# JSDM_Wemos_DS3231_Single_Layer.net
KiCad netlist of a schematic drawn in EAGLE
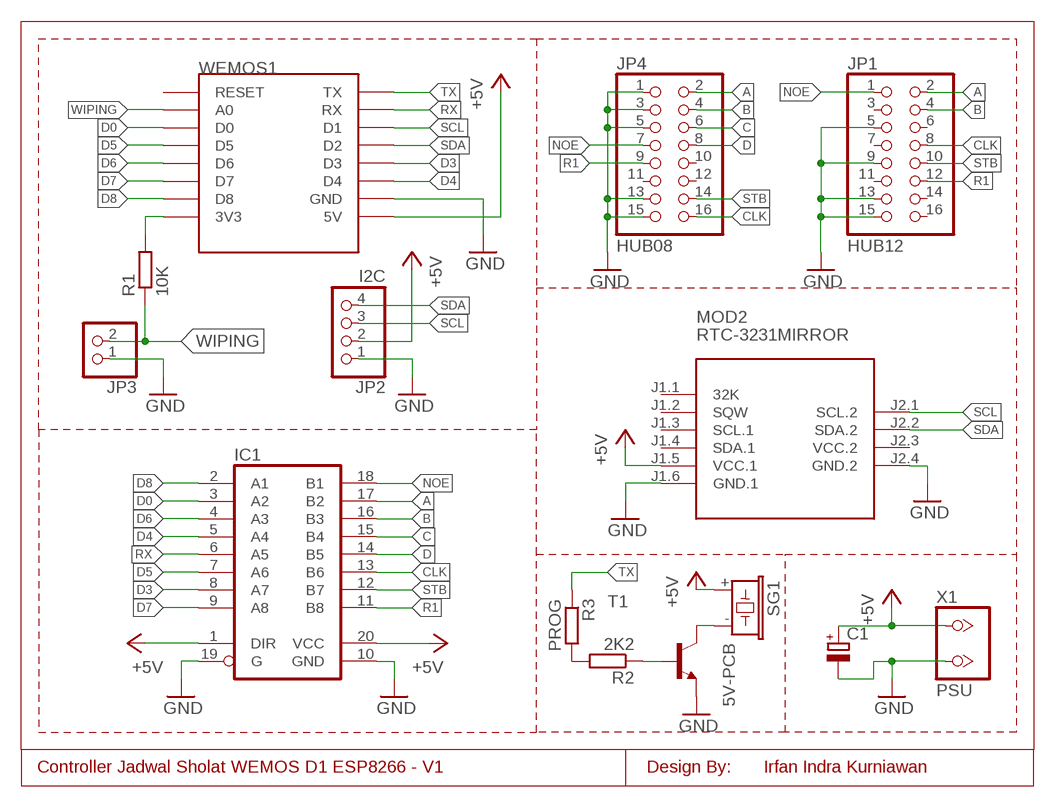
[diagram p0: schematic, sheet 1]

(export (version "E")
  (design (tool "Eeschema 10.0.6"))
  (components
    (comp (ref "C1")
      (value "CPOL-EUE3.5-8")
      (footprint "eagle-import:E3,5-8")
      (libsource (lib "eagle-import") (part "CPOL-EUE3.5-8"))
    )
    (comp (ref "IC1")
      (value "74245SMD")
      (footprint "eagle-import:SO20")
      (libsource (lib "eagle-import") (part "74245SMD"))
    )
    (comp (ref "JP1")
      (value "HUB12")
      (footprint "eagle-import:2X08")
      (libsource (lib "eagle-import") (part "PINHD-2X8"))
    )
    (comp (ref "JP2")
      (value "I2C")
      (footprint "eagle-import:1X04")
      (libsource (lib "eagle-import") (part "PINHD-1X4"))
    )
    (comp (ref "JP3")
      (value "PINHD-1X2")
      (footprint "eagle-import:1X02")
      (libsource (lib "eagle-import") (part "PINHD-1X2"))
    )
    (comp (ref "JP4")
      (value "HUB08")
      (footprint "eagle-import:2X08")
      (libsource (lib "eagle-import") (part "PINHD-2X8"))
    )
    (comp (ref "MOD2")
      (value "RTC-3231MIRROR")
      (footprint "eagle-import:RTC-DS3231-MIRROR")
      (libsource (lib "eagle-import") (part "RTC-3231MIRROR"))
    )
    (comp (ref "R1")
      (value "10K")
      (footprint "eagle-import:0207_12")
      (libsource (lib "eagle-import") (part "R-EU_0207/12"))
    )
    (comp (ref "R2")
      (value "2K2")
      (footprint "eagle-import:0207_7")
      (libsource (lib "eagle-import") (part "R-EU_0207/7"))
    )
    (comp (ref "R3")
      (value "PROG")
      (footprint "eagle-import:M0805")
      (libsource (lib "eagle-import") (part "R-EU_M0805"))
    )
    (comp (ref "SG1")
      (value "5V-PCB")
      (footprint "eagle-import:5V")
      (libsource (lib "eagle-import") (part "5V-PCB"))
    )
    (comp (ref "T1")
      (value "BC317-NPN-TO92-EBC")
      (footprint "eagle-import:TO92-EBC")
      (libsource (lib "eagle-import") (part "-NPN-TO92-EBCBC317"))
    )
    (comp (ref "WEMOS1")
      (value "WEMOS-D1-MINI")
      (footprint "eagle-import:WEMOS-D1-MINI")
      (libsource (lib "eagle-import") (part "WEMOS-D1-MINI"))
    )
    (comp (ref "X1")
      (value "PSU")
      (footprint "eagle-import:TB2")
      (libsource (lib "eagle-import") (part "2PIN"))
    )
  )
  (nets
    (net (code "1") (name "+5V") (class "Default")
      (node (ref "C1") (pin "+") (pinfunction "+_+") (pintype "passive"))
      (node (ref "IC1") (pin "1") (pinfunction "DIR_1") (pintype "input"))
      (node (ref "IC1") (pin "20") (pinfunction "VCC_20") (pintype "power_in"))
      (node (ref "JP2") (pin "2") (pinfunction "2_2") (pintype "passive"))
      (node (ref "MOD2") (pin "J1.5") (pinfunction "VCC.1_J1.5") (pintype "power_in"))
      (node (ref "SG1") (pin "+") (pinfunction "1_+") (pintype "passive"))
      (node (ref "WEMOS1") (pin "5V") (pinfunction "5V_5V") (pintype "bidirectional"))
      (node (ref "X1") (pin "1") (pinfunction "1_1") (pintype "bidirectional"))
    )
    (net (code "2") (name "/VCC.2") (class "Default")
      (node (ref "MOD2") (pin "J2.3") (pinfunction "VCC.2_J2.3") (pintype "power_in"))
    )
    (net (code "3") (name "A") (class "Default")
      (node (ref "IC1") (pin "17") (pinfunction "B2_17") (pintype "bidirectional"))
      (node (ref "JP1") (pin "2") (pinfunction "2_2") (pintype "passive"))
      (node (ref "JP4") (pin "2") (pinfunction "2_2") (pintype "passive"))
    )
    (net (code "4") (name "B") (class "Default")
      (node (ref "IC1") (pin "16") (pinfunction "B3_16") (pintype "bidirectional"))
      (node (ref "JP1") (pin "4") (pinfunction "4_4") (pintype "passive"))
      (node (ref "JP4") (pin "4") (pinfunction "4_4") (pintype "passive"))
    )
    (net (code "5") (name "C") (class "Default")
      (node (ref "IC1") (pin "15") (pinfunction "B4_15") (pintype "bidirectional"))
      (node (ref "JP4") (pin "6") (pinfunction "6_6") (pintype "passive"))
    )
    (net (code "6") (name "CLK") (class "Default")
      (node (ref "IC1") (pin "13") (pinfunction "B6_13") (pintype "bidirectional"))
      (node (ref "JP1") (pin "8") (pinfunction "8_8") (pintype "passive"))
      (node (ref "JP4") (pin "16") (pinfunction "16_16") (pintype "passive"))
    )
    (net (code "7") (name "D") (class "Default")
      (node (ref "IC1") (pin "14") (pinfunction "B5_14") (pintype "bidirectional"))
      (node (ref "JP4") (pin "8") (pinfunction "8_8") (pintype "passive"))
    )
    (net (code "8") (name "D0") (class "Default")
      (node (ref "IC1") (pin "3") (pinfunction "A2_3") (pintype "bidirectional"))
      (node (ref "WEMOS1") (pin "D0") (pinfunction "D0_D0") (pintype "bidirectional"))
    )
    (net (code "9") (name "D3") (class "Default")
      (node (ref "IC1") (pin "8") (pinfunction "A7_8") (pintype "bidirectional"))
      (node (ref "WEMOS1") (pin "D3") (pinfunction "D3_D3") (pintype "bidirectional"))
    )
    (net (code "10") (name "D4") (class "Default")
      (node (ref "IC1") (pin "5") (pinfunction "A4_5") (pintype "bidirectional"))
      (node (ref "WEMOS1") (pin "D4") (pinfunction "D4_D4") (pintype "bidirectional"))
    )
    (net (code "11") (name "D5") (class "Default")
      (node (ref "IC1") (pin "7") (pinfunction "A6_7") (pintype "bidirectional"))
      (node (ref "WEMOS1") (pin "D5") (pinfunction "D5_D5") (pintype "bidirectional"))
    )
    (net (code "12") (name "D6") (class "Default")
      (node (ref "IC1") (pin "4") (pinfunction "A3_4") (pintype "bidirectional"))
      (node (ref "WEMOS1") (pin "D6") (pinfunction "D6_D6") (pintype "bidirectional"))
    )
    (net (code "13") (name "D7") (class "Default")
      (node (ref "IC1") (pin "9") (pinfunction "A8_9") (pintype "bidirectional"))
      (node (ref "WEMOS1") (pin "D7") (pinfunction "D7_D7") (pintype "bidirectional"))
    )
    (net (code "14") (name "D8") (class "Default")
      (node (ref "IC1") (pin "2") (pinfunction "A1_2") (pintype "bidirectional"))
      (node (ref "WEMOS1") (pin "D8") (pinfunction "D8_D8") (pintype "bidirectional"))
    )
    (net (code "15") (name "GND") (class "Default")
      (node (ref "C1") (pin "-") (pinfunction "-_-") (pintype "passive"))
      (node (ref "IC1") (pin "10") (pinfunction "GND_10") (pintype "power_in"))
      (node (ref "IC1") (pin "19") (pinfunction "G_19") (pintype "input"))
      (node (ref "JP1") (pin "13") (pinfunction "13_13") (pintype "passive"))
      (node (ref "JP1") (pin "15") (pinfunction "15_15") (pintype "passive"))
      (node (ref "JP1") (pin "5") (pinfunction "5_5") (pintype "passive"))
      (node (ref "JP1") (pin "9") (pinfunction "9_9") (pintype "passive"))
      (node (ref "JP2") (pin "1") (pinfunction "1_1") (pintype "passive"))
      (node (ref "JP3") (pin "1") (pinfunction "1_1") (pintype "passive"))
      (node (ref "JP4") (pin "1") (pinfunction "1_1") (pintype "passive"))
      (node (ref "JP4") (pin "13") (pinfunction "13_13") (pintype "passive"))
      (node (ref "JP4") (pin "15") (pinfunction "15_15") (pintype "passive"))
      (node (ref "JP4") (pin "3") (pinfunction "3_3") (pintype "passive"))
      (node (ref "JP4") (pin "5") (pinfunction "5_5") (pintype "passive"))
      (node (ref "MOD2") (pin "J1.6") (pinfunction "GND.1_J1.6") (pintype "power_in"))
      (node (ref "MOD2") (pin "J2.4") (pinfunction "GND.2_J2.4") (pintype "power_in"))
      (node (ref "T1") (pin "E") (pinfunction "E_E") (pintype "passive"))
      (node (ref "WEMOS1") (pin "GND") (pinfunction "GND_GND") (pintype "bidirectional"))
      (node (ref "X1") (pin "2") (pinfunction "2_2") (pintype "bidirectional"))
    )
    (net (code "16") (name "NOE") (class "Default")
      (node (ref "IC1") (pin "18") (pinfunction "B1_18") (pintype "bidirectional"))
      (node (ref "JP1") (pin "1") (pinfunction "1_1") (pintype "passive"))
      (node (ref "JP4") (pin "7") (pinfunction "7_7") (pintype "passive"))
    )
    (net (code "17") (name "Net-(R1-Pad2)") (class "Default")
      (node (ref "R1") (pin "2") (pinfunction "2_2") (pintype "passive"))
      (node (ref "WEMOS1") (pin "3V3") (pinfunction "3V3_3V3") (pintype "bidirectional"))
    )
    (net (code "18") (name "Net-(R2-Pad1)") (class "Default")
      (node (ref "R2") (pin "1") (pinfunction "1_1") (pintype "passive"))
      (node (ref "T1") (pin "B") (pinfunction "B_B") (pintype "passive"))
    )
    (net (code "19") (name "Net-(R2-Pad2)") (class "Default")
      (node (ref "R2") (pin "2") (pinfunction "2_2") (pintype "passive"))
      (node (ref "R3") (pin "2") (pinfunction "2_2") (pintype "passive"))
    )
    (net (code "20") (name "Net-(SG1-2)") (class "Default")
      (node (ref "SG1") (pin "-") (pinfunction "2_-") (pintype "passive"))
      (node (ref "T1") (pin "C") (pinfunction "C_C") (pintype "passive"))
    )
    (net (code "21") (name "R1") (class "Default")
      (node (ref "IC1") (pin "11") (pinfunction "B8_11") (pintype "bidirectional"))
      (node (ref "JP1") (pin "12") (pinfunction "12_12") (pintype "passive"))
      (node (ref "JP4") (pin "9") (pinfunction "9_9") (pintype "passive"))
    )
    (net (code "22") (name "RX") (class "Default")
      (node (ref "IC1") (pin "6") (pinfunction "A5_6") (pintype "bidirectional"))
      (node (ref "WEMOS1") (pin "RX") (pinfunction "RX_RX") (pintype "bidirectional"))
    )
    (net (code "23") (name "SCL") (class "Default")
      (node (ref "JP2") (pin "3") (pinfunction "3_3") (pintype "passive"))
      (node (ref "MOD2") (pin "J2.1") (pinfunction "SCL.2_J2.1") (pintype "bidirectional"))
      (node (ref "WEMOS1") (pin "D1") (pinfunction "D1_D1") (pintype "bidirectional"))
    )
    (net (code "24") (name "SDA") (class "Default")
      (node (ref "JP2") (pin "4") (pinfunction "4_4") (pintype "passive"))
      (node (ref "MOD2") (pin "J2.2") (pinfunction "SDA.2_J2.2") (pintype "bidirectional"))
      (node (ref "WEMOS1") (pin "D2") (pinfunction "D2_D2") (pintype "bidirectional"))
    )
    (net (code "25") (name "STB") (class "Default")
      (node (ref "IC1") (pin "12") (pinfunction "B7_12") (pintype "bidirectional"))
      (node (ref "JP1") (pin "10") (pinfunction "10_10") (pintype "passive"))
      (node (ref "JP4") (pin "14") (pinfunction "14_14") (pintype "passive"))
    )
    (net (code "26") (name "TX") (class "Default")
      (node (ref "R3") (pin "1") (pinfunction "1_1") (pintype "passive"))
      (node (ref "WEMOS1") (pin "TX") (pinfunction "TX_TX") (pintype "bidirectional"))
    )
    (net (code "27") (name "WIPING") (class "Default")
      (node (ref "JP3") (pin "2") (pinfunction "2_2") (pintype "passive"))
      (node (ref "R1") (pin "1") (pinfunction "1_1") (pintype "passive"))
      (node (ref "WEMOS1") (pin "A0") (pinfunction "A0_A0") (pintype "bidirectional"))
    )
    (net (code "28") (name "unconnected-(JP1-Pad3)") (class "Default")
      (node (ref "JP1") (pin "3") (pinfunction "3_3") (pintype "passive"))
    )
    (net (code "29") (name "unconnected-(JP1-Pad6)") (class "Default")
      (node (ref "JP1") (pin "6") (pinfunction "6_6") (pintype "passive"))
    )
    (net (code "30") (name "unconnected-(JP1-Pad7)") (class "Default")
      (node (ref "JP1") (pin "7") (pinfunction "7_7") (pintype "passive"))
    )
    (net (code "31") (name "unconnected-(JP1-Pad11)") (class "Default")
      (node (ref "JP1") (pin "11") (pinfunction "11_11") (pintype "passive"))
    )
    (net (code "32") (name "unconnected-(JP1-Pad14)") (class "Default")
      (node (ref "JP1") (pin "14") (pinfunction "14_14") (pintype "passive"))
    )
    (net (code "33") (name "unconnected-(JP1-Pad16)") (class "Default")
      (node (ref "JP1") (pin "16") (pinfunction "16_16") (pintype "passive"))
    )
    (net (code "34") (name "unconnected-(JP4-Pad10)") (class "Default")
      (node (ref "JP4") (pin "10") (pinfunction "10_10") (pintype "passive"))
    )
    (net (code "35") (name "unconnected-(JP4-Pad11)") (class "Default")
      (node (ref "JP4") (pin "11") (pinfunction "11_11") (pintype "passive"))
    )
    (net (code "36") (name "unconnected-(JP4-Pad12)") (class "Default")
      (node (ref "JP4") (pin "12") (pinfunction "12_12") (pintype "passive"))
    )
    (net (code "37") (name "unconnected-(MOD2-32K-PadJ1.1)") (class "Default")
      (node (ref "MOD2") (pin "J1.1") (pinfunction "32K_J1.1") (pintype "bidirectional"))
    )
    (net (code "38") (name "unconnected-(MOD2-SCL.1-PadJ1.3)") (class "Default")
      (node (ref "MOD2") (pin "J1.3") (pinfunction "SCL.1_J1.3") (pintype "bidirectional"))
    )
    (net (code "39") (name "unconnected-(MOD2-SDA.1-PadJ1.4)") (class "Default")
      (node (ref "MOD2") (pin "J1.4") (pinfunction "SDA.1_J1.4") (pintype "bidirectional"))
    )
    (net (code "40") (name "unconnected-(MOD2-SQW-PadJ1.2)") (class "Default")
      (node (ref "MOD2") (pin "J1.2") (pinfunction "SQW_J1.2") (pintype "bidirectional"))
    )
    (net (code "41") (name "unconnected-(WEMOS1-PadRESET)") (class "Default")
      (node (ref "WEMOS1") (pin "RESET") (pinfunction "RESET_RESET") (pintype "bidirectional"))
    )
  )
)
